# ATTAMI-Shield-Servo.net
KiCad netlist of a schematic drawn in EAGLE
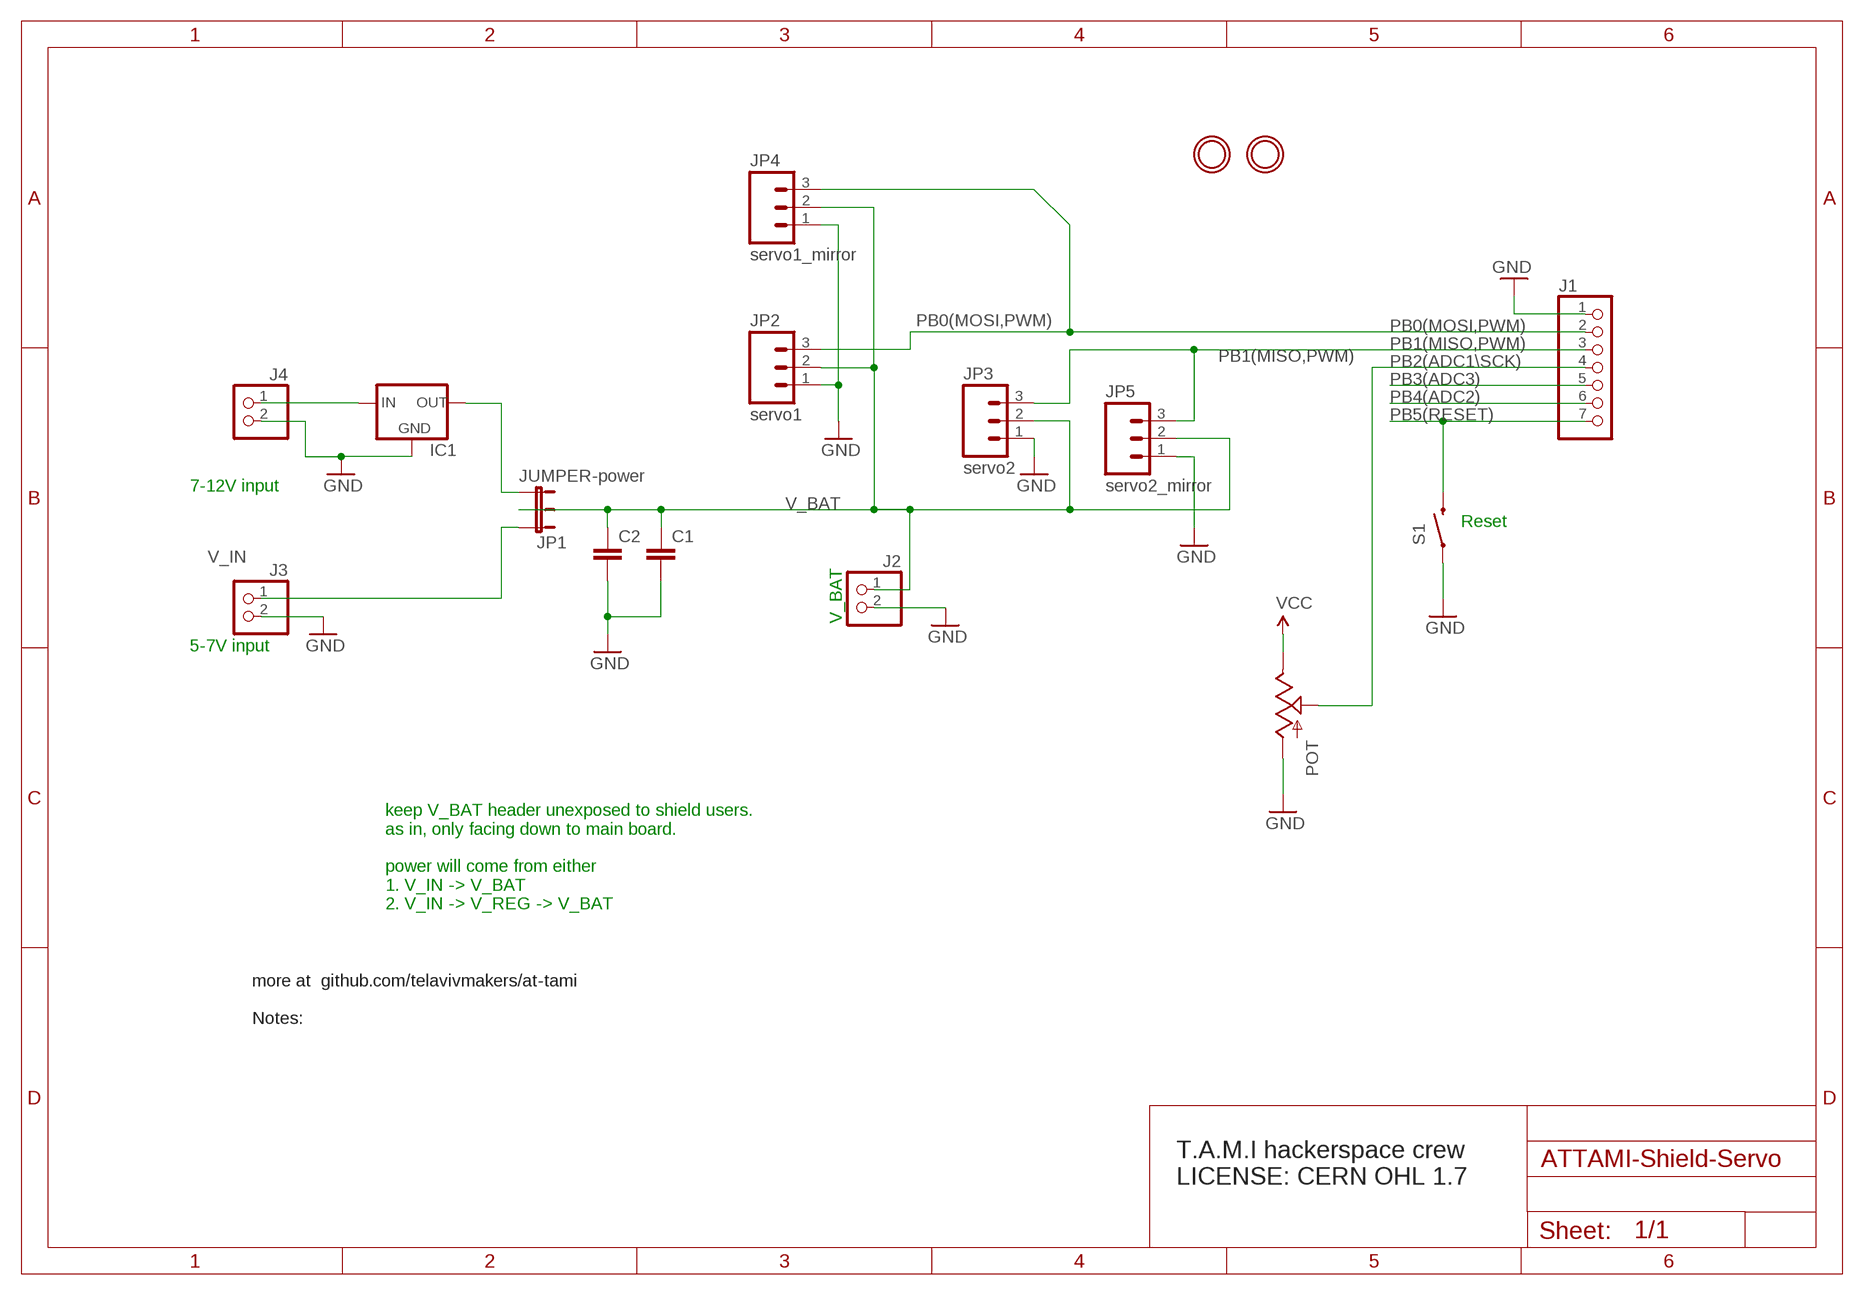
[diagram p0: schematic, sheet 1]

(export (version "E")
  (design (tool "Eeschema 10.0.6"))
  (components
    (comp (ref "C1")
      (value "CAPKIT")
      (footprint "eagle-import:CAP-PTH-SMALL-KIT")
      (libsource (lib "eagle-import") (part "CAPKIT"))
    )
    (comp (ref "C2")
      (value "CAPKIT")
      (footprint "eagle-import:CAP-PTH-SMALL-KIT")
      (libsource (lib "eagle-import") (part "CAPKIT"))
    )
    (comp (ref "IC1")
      (value "V_REG_78XXSINK")
      (footprint "eagle-import:TO220-IGO")
      (libsource (lib "eagle-import") (part "V_REG_78XXSINK"))
    )
    (comp (ref "J1")
      (value "HEADER-1X7ROUND")
      (footprint "eagle-import:1X07_ROUND")
      (libsource (lib "eagle-import") (part "HEADER-1X7ROUND"))
    )
    (comp (ref "J2")
      (value "HEADER-1X2ROUND")
      (footprint "eagle-import:1X02_ROUND")
      (libsource (lib "eagle-import") (part "HEADER-1X2ROUND"))
    )
    (comp (ref "J3")
      (value "HEADER-1X2ROUND")
      (footprint "eagle-import:1X02_ROUND")
      (libsource (lib "eagle-import") (part "HEADER-1X2ROUND"))
    )
    (comp (ref "J4")
      (value "HEADER-1X2ROUND")
      (footprint "eagle-import:1X02_ROUND")
      (libsource (lib "eagle-import") (part "HEADER-1X2ROUND"))
    )
    (comp (ref "JP1")
      (value "JUMPER-power")
      (footprint "eagle-import:1X03")
      (libsource (lib "eagle-import") (part "JUMPER-3PTH"))
    )
    (comp (ref "JP2")
      (value "servo1")
      (footprint "eagle-import:1X03_LONGPADS")
      (libsource (lib "eagle-import") (part "M03LONGPADS"))
    )
    (comp (ref "JP3")
      (value "servo2")
      (footprint "eagle-import:1X03_LONGPADS")
      (libsource (lib "eagle-import") (part "M03LONGPADS"))
    )
    (comp (ref "JP4")
      (value "servo1_mirror")
      (footprint "eagle-import:1X03_LONGPADS")
      (libsource (lib "eagle-import") (part "M03LONGPADS"))
    )
    (comp (ref "JP5")
      (value "servo2_mirror")
      (footprint "eagle-import:1X03_LONGPADS")
      (libsource (lib "eagle-import") (part "M03LONGPADS"))
    )
    (comp (ref "POT")
      (value "POT100K_3362U")
      (footprint "eagle-import:3362U")
      (libsource (lib "eagle-import") (part "POT100K_3362U"))
    )
    (comp (ref "S1")
      (value "SWITCH-MOMENTARY-2-SMD-1101NE")
      (footprint "eagle-import:TACTILE-SWITCH-1101NE")
      (libsource (lib "eagle-import") (part "SWITCH-MOMENTARY-2-SMD-1101NE"))
    )
    (comp (ref "U$1")
      (value "MOUNTINGHOLE2.0")
      (footprint "eagle-import:MOUNTINGHOLE_2.0_PLATED")
      (libsource (lib "eagle-import") (part "MOUNTINGHOLE2.0"))
    )
    (comp (ref "U$2")
      (value "MOUNTINGHOLE2.0")
      (footprint "eagle-import:MOUNTINGHOLE_2.0_PLATED")
      (libsource (lib "eagle-import") (part "MOUNTINGHOLE2.0"))
    )
  )
  (nets
    (net (code "1") (name "/PB0(MOSI,PWM)") (class "Default")
      (node (ref "J1") (pin "2") (pinfunction "2_2") (pintype "passive"))
      (node (ref "JP2") (pin "3") (pinfunction "3_3") (pintype "passive"))
      (node (ref "JP4") (pin "3") (pinfunction "3_3") (pintype "passive"))
    )
    (net (code "2") (name "/PB1(MISO,PWM)") (class "Default")
      (node (ref "J1") (pin "3") (pinfunction "3_3") (pintype "passive"))
      (node (ref "JP3") (pin "3") (pinfunction "3_3") (pintype "passive"))
      (node (ref "JP5") (pin "3") (pinfunction "3_3") (pintype "passive"))
    )
    (net (code "3") (name "/PB2(ADC1\\SCK)") (class "Default")
      (node (ref "J1") (pin "4") (pinfunction "4_4") (pintype "passive"))
      (node (ref "POT") (pin "P$2") (pinfunction "S_P$2") (pintype "passive"))
    )
    (net (code "4") (name "/PB3(ADC3)") (class "Default")
      (node (ref "J1") (pin "5") (pinfunction "5_5") (pintype "passive"))
    )
    (net (code "5") (name "/PB4(ADC2)") (class "Default")
      (node (ref "J1") (pin "6") (pinfunction "6_6") (pintype "passive"))
    )
    (net (code "6") (name "/PB5(RESET)") (class "Default")
      (node (ref "J1") (pin "7") (pinfunction "7_7") (pintype "passive"))
      (node (ref "S1") (pin "P$2") (pinfunction "2_P$2") (pintype "passive"))
    )
    (net (code "7") (name "/V_BAT") (class "Default")
      (node (ref "C1") (pin "1") (pinfunction "1_1") (pintype "passive"))
      (node (ref "C2") (pin "1") (pinfunction "1_1") (pintype "passive"))
      (node (ref "J2") (pin "1") (pinfunction "1_1") (pintype "passive"))
      (node (ref "JP1") (pin "2") (pinfunction "2_2") (pintype "passive"))
      (node (ref "JP2") (pin "2") (pinfunction "2_2") (pintype "passive"))
      (node (ref "JP3") (pin "2") (pinfunction "2_2") (pintype "passive"))
      (node (ref "JP4") (pin "2") (pinfunction "2_2") (pintype "passive"))
      (node (ref "JP5") (pin "2") (pinfunction "2_2") (pintype "passive"))
    )
    (net (code "8") (name "/V_IN") (class "Default")
      (node (ref "J3") (pin "1") (pinfunction "1_1") (pintype "passive"))
      (node (ref "JP1") (pin "1") (pinfunction "1_1") (pintype "passive"))
    )
    (net (code "9") (name "GND") (class "Default")
      (node (ref "C1") (pin "2") (pinfunction "2_2") (pintype "passive"))
      (node (ref "C2") (pin "2") (pinfunction "2_2") (pintype "passive"))
      (node (ref "IC1") (pin "GND") (pinfunction "GND_GND") (pintype "input"))
      (node (ref "J1") (pin "1") (pinfunction "1_1") (pintype "passive"))
      (node (ref "J2") (pin "2") (pinfunction "2_2") (pintype "passive"))
      (node (ref "J3") (pin "2") (pinfunction "2_2") (pintype "passive"))
      (node (ref "J4") (pin "2") (pinfunction "2_2") (pintype "passive"))
      (node (ref "JP2") (pin "1") (pinfunction "1_1") (pintype "passive"))
      (node (ref "JP3") (pin "1") (pinfunction "1_1") (pintype "passive"))
      (node (ref "JP4") (pin "1") (pinfunction "1_1") (pintype "passive"))
      (node (ref "JP5") (pin "1") (pinfunction "1_1") (pintype "passive"))
      (node (ref "POT") (pin "P$3") (pinfunction "A_P$3") (pintype "passive"))
      (node (ref "S1") (pin "P$1") (pinfunction "1_P$1") (pintype "passive"))
    )
    (net (code "10") (name "Net-(IC1-PadIN)") (class "Default")
      (node (ref "IC1") (pin "IN") (pinfunction "IN_IN") (pintype "input"))
      (node (ref "J4") (pin "1") (pinfunction "1_1") (pintype "passive"))
    )
    (net (code "11") (name "Net-(IC1-PadOUT)") (class "Default")
      (node (ref "IC1") (pin "OUT") (pinfunction "OUT_OUT") (pintype "output"))
      (node (ref "JP1") (pin "3") (pinfunction "3_3") (pintype "passive"))
    )
    (net (code "12") (name "VCC") (class "Default")
      (node (ref "POT") (pin "P$1") (pinfunction "E_P$1") (pintype "passive"))
    )
  )
)
